# Attiny13.net
KiCad netlist of a schematic drawn in EAGLE
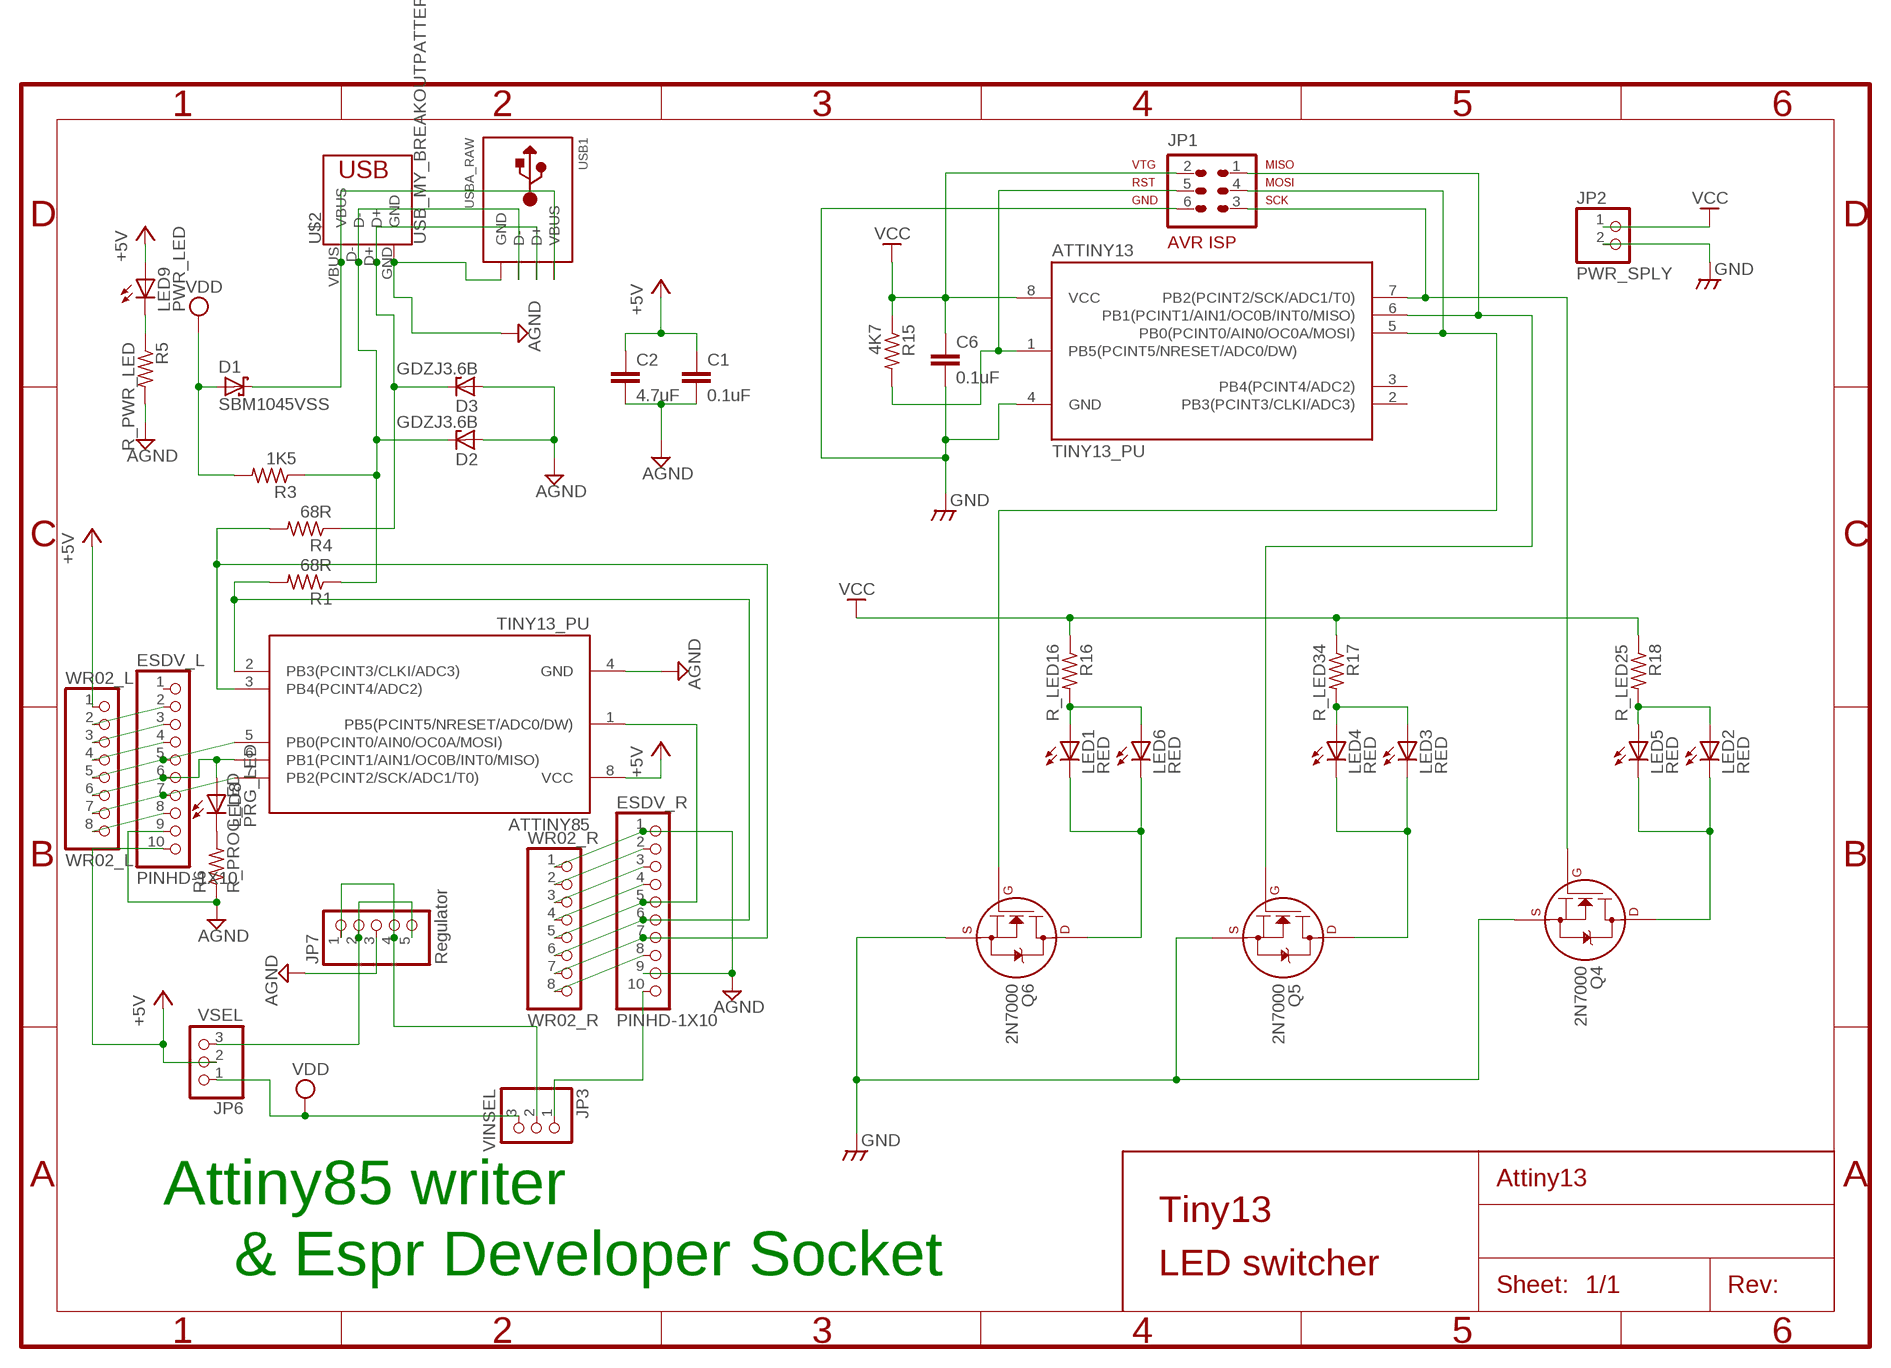
[diagram p0: schematic, sheet 1]

(export (version "E")
  (design (tool "Eeschema 10.0.6"))
  (components
    (comp (ref "ATTINY13")
      (value "TINY13_PU")
      (footprint "eagle-import:TINY_DIL08")
      (libsource (lib "eagle-import") (part "TINY13_PU"))
    )
    (comp (ref "ATTINY85")
      (value "TINY13_PU")
      (footprint "eagle-import:TINY_DIL08")
      (libsource (lib "eagle-import") (part "TINY13_PU"))
    )
    (comp (ref "C1")
      (value "0.1uF")
      (footprint "eagle-import:C050-025X075")
      (libsource (lib "eagle-import") (part "C-EU050-025X075"))
    )
    (comp (ref "C2")
      (value "4.7uF")
      (footprint "eagle-import:C050-025X075")
      (libsource (lib "eagle-import") (part "C-EU050-025X075"))
    )
    (comp (ref "C6")
      (value "0.1uF")
      (footprint "eagle-import:C050-025X075")
      (libsource (lib "eagle-import") (part "C-EU050-025X075"))
    )
    (comp (ref "D1")
      (value "SBM1045VSS")
      (footprint "eagle-import:DO41-10")
      (libsource (lib "eagle-import") (part "SCHOTTKY-DIODEDO41"))
    )
    (comp (ref "D2")
      (value "GDZJ3.6B")
      (footprint "eagle-import:DO34Z7")
      (libsource (lib "eagle-import") (part "ZENER-DIODEDO34-7"))
    )
    (comp (ref "D3")
      (value "GDZJ3.6B")
      (footprint "eagle-import:DO34Z7")
      (libsource (lib "eagle-import") (part "ZENER-DIODEDO34-7"))
    )
    (comp (ref "ESDV_L")
      (value "PINHD-1X10")
      (footprint "eagle-import:1X10-BIG")
      (libsource (lib "eagle-import") (part "PINHD-1X10"))
    )
    (comp (ref "ESDV_R")
      (value "PINHD-1X10")
      (footprint "eagle-import:1X10-BIG")
      (libsource (lib "eagle-import") (part "PINHD-1X10"))
    )
    (comp (ref "JP1")
      (value "AVR-ISP-6")
      (footprint "eagle-import:AVR-ISP-6")
      (libsource (lib "eagle-import") (part "AVR-ISP-6"))
    )
    (comp (ref "JP2")
      (value "PWR_SPLY")
      (footprint "eagle-import:1X02")
      (libsource (lib "eagle-import") (part "PINHD-1X2"))
    )
    (comp (ref "JP3")
      (value "VINSEL")
      (footprint "eagle-import:1X03")
      (libsource (lib "eagle-import") (part "PINHD-1X3"))
    )
    (comp (ref "JP6")
      (value "VSEL")
      (footprint "eagle-import:1X03")
      (libsource (lib "eagle-import") (part "PINHD-1X3"))
    )
    (comp (ref "JP7")
      (value "Regulator")
      (footprint "eagle-import:1X05")
      (libsource (lib "eagle-import") (part "PINHD-1X5"))
    )
    (comp (ref "LED1")
      (value "RED")
      (footprint "eagle-import:SFH480")
      (libsource (lib "eagle-import") (part "led_LEDSFH480"))
    )
    (comp (ref "LED2")
      (value "RED")
      (footprint "eagle-import:SFH480")
      (libsource (lib "eagle-import") (part "led_LEDSFH480"))
    )
    (comp (ref "LED3")
      (value "RED")
      (footprint "eagle-import:SFH480")
      (libsource (lib "eagle-import") (part "led_LEDSFH480"))
    )
    (comp (ref "LED4")
      (value "RED")
      (footprint "eagle-import:SFH480")
      (libsource (lib "eagle-import") (part "led_LEDSFH480"))
    )
    (comp (ref "LED5")
      (value "RED")
      (footprint "eagle-import:SFH480")
      (libsource (lib "eagle-import") (part "led_LEDSFH480"))
    )
    (comp (ref "LED6")
      (value "RED")
      (footprint "eagle-import:SFH480")
      (libsource (lib "eagle-import") (part "led_LEDSFH480"))
    )
    (comp (ref "LED8")
      (value "PRG_LED")
      (footprint "eagle-import:SFH480")
      (libsource (lib "eagle-import") (part "LEDSFH480"))
    )
    (comp (ref "LED9")
      (value "PWR_LED")
      (footprint "eagle-import:SFH480")
      (libsource (lib "eagle-import") (part "LEDSFH480"))
    )
    (comp (ref "Q4")
      (value "2N7000")
      (footprint "eagle-import:TO-92")
      (libsource (lib "eagle-import") (part "2N700_TO920"))
    )
    (comp (ref "Q5")
      (value "2N7000")
      (footprint "eagle-import:TO-92")
      (libsource (lib "eagle-import") (part "2N700_TO920"))
    )
    (comp (ref "Q6")
      (value "2N7000")
      (footprint "eagle-import:TO-92")
      (libsource (lib "eagle-import") (part "2N700_TO920"))
    )
    (comp (ref "R1")
      (value "68R")
      (footprint "eagle-import:0204_7")
      (libsource (lib "eagle-import") (part "R-US_0204/7"))
    )
    (comp (ref "R3")
      (value "1K5")
      (footprint "eagle-import:0204_7")
      (libsource (lib "eagle-import") (part "R-US_0204/7"))
    )
    (comp (ref "R4")
      (value "68R")
      (footprint "eagle-import:0204_7")
      (libsource (lib "eagle-import") (part "R-US_0204/7"))
    )
    (comp (ref "R5")
      (value "R_PWR_LED")
      (footprint "eagle-import:0204_7")
      (libsource (lib "eagle-import") (part "R-US_0204/7"))
    )
    (comp (ref "R6")
      (value "R_PROG_LED")
      (footprint "eagle-import:0204_7")
      (libsource (lib "eagle-import") (part "R-US_0204/7"))
    )
    (comp (ref "R15")
      (value "4K7")
      (footprint "eagle-import:0204_7")
      (libsource (lib "eagle-import") (part "R-US_0204/7"))
    )
    (comp (ref "R16")
      (value "R_LED16")
      (footprint "eagle-import:0204_7")
      (libsource (lib "eagle-import") (part "R-US_0204/7"))
    )
    (comp (ref "R17")
      (value "R_LED34")
      (footprint "eagle-import:0204_7")
      (libsource (lib "eagle-import") (part "R-US_0204/7"))
    )
    (comp (ref "R18")
      (value "R_LED25")
      (footprint "eagle-import:0204_7")
      (libsource (lib "eagle-import") (part "R-US_0204/7"))
    )
    (comp (ref "U$2")
      (value "USB_MY_BREAKOUTPATTERN2")
      (footprint "eagle-import:USB_MY_BREAKOUT2")
      (libsource (lib "eagle-import") (part "USB_MY_BREAKOUTPATTERN2"))
    )
    (comp (ref "USB1")
      (value "USBA_RAW")
      (footprint "eagle-import:USBA_RAW")
      (libsource (lib "eagle-import") (part "USBA_RAW"))
    )
    (comp (ref "WR02_L")
      (value "WR02_L")
      (footprint "eagle-import:1X08-BIG")
      (libsource (lib "eagle-import") (part "PINHD-1X8BIG"))
    )
    (comp (ref "WR02_R")
      (value "WR02_R")
      (footprint "eagle-import:1X08-BIG")
      (libsource (lib "eagle-import") (part "PINHD-1X8BIG"))
    )
  )
  (nets
    (net (code "1") (name "+5V") (class "Default")
      (node (ref "ATTINY85") (pin "8") (pinfunction "VCC_8") (pintype "power_in"))
      (node (ref "C1") (pin "1") (pinfunction "1_1") (pintype "passive"))
      (node (ref "C2") (pin "1") (pinfunction "1_1") (pintype "passive"))
      (node (ref "ESDV_L") (pin "10") (pinfunction "10_10") (pintype "passive"))
      (node (ref "JP6") (pin "2") (pinfunction "2_2") (pintype "passive"))
      (node (ref "LED9") (pin "A") (pinfunction "A_A") (pintype "passive"))
      (node (ref "WR02_L") (pin "1") (pinfunction "1_1") (pintype "passive"))
    )
    (net (code "2") (name "AGND") (class "Default")
      (node (ref "ATTINY85") (pin "4") (pinfunction "GND_4") (pintype "power_in"))
      (node (ref "C1") (pin "2") (pinfunction "2_2") (pintype "passive"))
      (node (ref "C2") (pin "2") (pinfunction "2_2") (pintype "passive"))
      (node (ref "D2") (pin "A") (pinfunction "A_A") (pintype "passive"))
      (node (ref "D3") (pin "A") (pinfunction "A_A") (pintype "passive"))
      (node (ref "ESDV_L") (pin "9") (pinfunction "9_9") (pintype "passive"))
      (node (ref "ESDV_R") (pin "1") (pinfunction "1_1") (pintype "passive"))
      (node (ref "ESDV_R") (pin "9") (pinfunction "9_9") (pintype "passive"))
      (node (ref "JP7") (pin "3") (pinfunction "3_3") (pintype "passive"))
      (node (ref "R5") (pin "2") (pinfunction "2_2") (pintype "passive"))
      (node (ref "R6") (pin "1") (pinfunction "1_1") (pintype "passive"))
      (node (ref "U$2") (pin "GND") (pinfunction "GND_GND") (pintype "power_in"))
      (node (ref "USB1") (pin "GND") (pinfunction "GND_GND") (pintype "power_in"))
      (node (ref "WR02_R") (pin "1") (pinfunction "1_1") (pintype "passive"))
    )
    (net (code "3") (name "GND") (class "Default")
      (node (ref "ATTINY13") (pin "4") (pinfunction "GND_4") (pintype "power_in"))
      (node (ref "C6") (pin "2") (pinfunction "2_2") (pintype "passive"))
      (node (ref "JP1") (pin "6") (pinfunction "6_6") (pintype "passive"))
      (node (ref "JP2") (pin "2") (pinfunction "2_2") (pintype "passive"))
      (node (ref "Q4") (pin "1") (pinfunction "S_1") (pintype "bidirectional"))
      (node (ref "Q5") (pin "1") (pinfunction "S_1") (pintype "bidirectional"))
      (node (ref "Q6") (pin "1") (pinfunction "S_1") (pintype "bidirectional"))
    )
    (net (code "4") (name "Net-(ATTINY13-PB0(PCINT0{slash}AIN0{slash}OC0A{slash}MOSI))") (class "Default")
      (node (ref "ATTINY13") (pin "5") (pinfunction "PB0(PCINT0/AIN0/OC0A/MOSI)_5") (pintype "bidirectional"))
      (node (ref "JP1") (pin "4") (pinfunction "4_4") (pintype "passive"))
      (node (ref "Q6") (pin "2") (pinfunction "G_2") (pintype "tri_state"))
    )
    (net (code "5") (name "Net-(ATTINY13-PB1(PCINT1{slash}AIN1{slash}OC0B{slash}INT0{slash}MISO))") (class "Default")
      (node (ref "ATTINY13") (pin "6") (pinfunction "PB1(PCINT1/AIN1/OC0B/INT0/MISO)_6") (pintype "bidirectional"))
      (node (ref "JP1") (pin "1") (pinfunction "1_1") (pintype "passive"))
      (node (ref "Q5") (pin "2") (pinfunction "G_2") (pintype "tri_state"))
    )
    (net (code "6") (name "Net-(ATTINY13-PB2(PCINT2{slash}SCK{slash}ADC1{slash}T0))") (class "Default")
      (node (ref "ATTINY13") (pin "7") (pinfunction "PB2(PCINT2/SCK/ADC1/T0)_7") (pintype "bidirectional"))
      (node (ref "JP1") (pin "3") (pinfunction "3_3") (pintype "passive"))
      (node (ref "Q4") (pin "2") (pinfunction "G_2") (pintype "tri_state"))
    )
    (net (code "7") (name "Net-(ATTINY13-PB5(PCINT5{slash}NRESET{slash}ADC0{slash}DW))") (class "Default")
      (node (ref "ATTINY13") (pin "1") (pinfunction "PB5(PCINT5/NRESET/ADC0/DW)_1") (pintype "bidirectional"))
      (node (ref "JP1") (pin "5") (pinfunction "5_5") (pintype "passive"))
      (node (ref "R15") (pin "2") (pinfunction "2_2") (pintype "passive"))
    )
    (net (code "8") (name "Net-(ATTINY85-PB0(PCINT0{slash}AIN0{slash}OC0A{slash}MOSI))") (class "Default")
      (node (ref "ATTINY85") (pin "5") (pinfunction "PB0(PCINT0/AIN0/OC0A/MOSI)_5") (pintype "bidirectional"))
      (node (ref "ESDV_L") (pin "5") (pinfunction "5_5") (pintype "passive"))
      (node (ref "WR02_L") (pin "5") (pinfunction "5_5") (pintype "passive"))
    )
    (net (code "9") (name "Net-(ATTINY85-PB1(PCINT1{slash}AIN1{slash}OC0B{slash}INT0{slash}MISO))") (class "Default")
      (node (ref "ATTINY85") (pin "6") (pinfunction "PB1(PCINT1/AIN1/OC0B/INT0/MISO)_6") (pintype "bidirectional"))
      (node (ref "ESDV_L") (pin "6") (pinfunction "6_6") (pintype "passive"))
      (node (ref "LED8") (pin "A") (pinfunction "A_A") (pintype "passive"))
      (node (ref "WR02_L") (pin "6") (pinfunction "6_6") (pintype "passive"))
    )
    (net (code "10") (name "Net-(ATTINY85-PB2(PCINT2{slash}SCK{slash}ADC1{slash}T0))") (class "Default")
      (node (ref "ATTINY85") (pin "7") (pinfunction "PB2(PCINT2/SCK/ADC1/T0)_7") (pintype "bidirectional"))
      (node (ref "ESDV_L") (pin "7") (pinfunction "7_7") (pintype "passive"))
      (node (ref "WR02_L") (pin "7") (pinfunction "7_7") (pintype "passive"))
    )
    (net (code "11") (name "Net-(ATTINY85-PB3(PCINT3{slash}CLKI{slash}ADC3))") (class "Default")
      (node (ref "ATTINY85") (pin "2") (pinfunction "PB3(PCINT3/CLKI/ADC3)_2") (pintype "bidirectional"))
      (node (ref "ESDV_R") (pin "6") (pinfunction "6_6") (pintype "passive"))
      (node (ref "R1") (pin "2") (pinfunction "2_2") (pintype "passive"))
      (node (ref "WR02_R") (pin "6") (pinfunction "6_6") (pintype "passive"))
    )
    (net (code "12") (name "Net-(ATTINY85-PB4(PCINT4{slash}ADC2))") (class "Default")
      (node (ref "ATTINY85") (pin "3") (pinfunction "PB4(PCINT4/ADC2)_3") (pintype "bidirectional"))
      (node (ref "ESDV_R") (pin "7") (pinfunction "7_7") (pintype "passive"))
      (node (ref "R4") (pin "2") (pinfunction "2_2") (pintype "passive"))
      (node (ref "WR02_R") (pin "7") (pinfunction "7_7") (pintype "passive"))
    )
    (net (code "13") (name "Net-(ATTINY85-PB5(PCINT5{slash}NRESET{slash}ADC0{slash}DW))") (class "Default")
      (node (ref "ATTINY85") (pin "1") (pinfunction "PB5(PCINT5/NRESET/ADC0/DW)_1") (pintype "bidirectional"))
      (node (ref "ESDV_R") (pin "5") (pinfunction "5_5") (pintype "passive"))
      (node (ref "WR02_R") (pin "5") (pinfunction "5_5") (pintype "passive"))
    )
    (net (code "14") (name "Net-(D1-PadC)") (class "Default")
      (node (ref "D1") (pin "C") (pinfunction "C_C") (pintype "passive"))
      (node (ref "U$2") (pin "VBUS") (pinfunction "VBUS_VBUS") (pintype "power_in"))
      (node (ref "USB1") (pin "VBUS") (pinfunction "VBUS_VBUS") (pintype "power_in"))
    )
    (net (code "15") (name "Net-(D2-PadC)") (class "Default")
      (node (ref "D2") (pin "C") (pinfunction "C_C") (pintype "passive"))
      (node (ref "R1") (pin "1") (pinfunction "1_1") (pintype "passive"))
      (node (ref "R3") (pin "1") (pinfunction "1_1") (pintype "passive"))
      (node (ref "U$2") (pin "D-") (pinfunction "D-_D-") (pintype "bidirectional"))
      (node (ref "USB1") (pin "D-") (pinfunction "D-_D-") (pintype "bidirectional"))
    )
    (net (code "16") (name "Net-(D3-PadC)") (class "Default")
      (node (ref "D3") (pin "C") (pinfunction "C_C") (pintype "passive"))
      (node (ref "R4") (pin "1") (pinfunction "1_1") (pintype "passive"))
      (node (ref "U$2") (pin "D+") (pinfunction "D+_D+") (pintype "bidirectional"))
      (node (ref "USB1") (pin "D+") (pinfunction "D+_D+") (pintype "bidirectional"))
    )
    (net (code "17") (name "Net-(ESDV_L-Pad2)") (class "Default")
      (node (ref "ESDV_L") (pin "2") (pinfunction "2_2") (pintype "passive"))
      (node (ref "WR02_L") (pin "2") (pinfunction "2_2") (pintype "passive"))
    )
    (net (code "18") (name "Net-(ESDV_L-Pad3)") (class "Default")
      (node (ref "ESDV_L") (pin "3") (pinfunction "3_3") (pintype "passive"))
      (node (ref "WR02_L") (pin "3") (pinfunction "3_3") (pintype "passive"))
    )
    (net (code "19") (name "Net-(ESDV_L-Pad4)") (class "Default")
      (node (ref "ESDV_L") (pin "4") (pinfunction "4_4") (pintype "passive"))
      (node (ref "WR02_L") (pin "4") (pinfunction "4_4") (pintype "passive"))
    )
    (net (code "20") (name "Net-(ESDV_L-Pad8)") (class "Default")
      (node (ref "ESDV_L") (pin "8") (pinfunction "8_8") (pintype "passive"))
      (node (ref "WR02_L") (pin "8") (pinfunction "8_8") (pintype "passive"))
    )
    (net (code "21") (name "Net-(ESDV_R-Pad2)") (class "Default")
      (node (ref "ESDV_R") (pin "2") (pinfunction "2_2") (pintype "passive"))
      (node (ref "WR02_R") (pin "2") (pinfunction "2_2") (pintype "passive"))
    )
    (net (code "22") (name "Net-(ESDV_R-Pad3)") (class "Default")
      (node (ref "ESDV_R") (pin "3") (pinfunction "3_3") (pintype "passive"))
      (node (ref "WR02_R") (pin "3") (pinfunction "3_3") (pintype "passive"))
    )
    (net (code "23") (name "Net-(ESDV_R-Pad4)") (class "Default")
      (node (ref "ESDV_R") (pin "4") (pinfunction "4_4") (pintype "passive"))
      (node (ref "WR02_R") (pin "4") (pinfunction "4_4") (pintype "passive"))
    )
    (net (code "24") (name "Net-(ESDV_R-Pad8)") (class "Default")
      (node (ref "ESDV_R") (pin "8") (pinfunction "8_8") (pintype "passive"))
      (node (ref "WR02_R") (pin "8") (pinfunction "8_8") (pintype "passive"))
    )
    (net (code "25") (name "Net-(ESDV_R-Pad10)") (class "Default")
      (node (ref "ESDV_R") (pin "10") (pinfunction "10_10") (pintype "passive"))
      (node (ref "JP3") (pin "1") (pinfunction "1_1") (pintype "passive"))
    )
    (net (code "26") (name "Net-(JP3-Pad2)") (class "Default")
      (node (ref "JP3") (pin "2") (pinfunction "2_2") (pintype "passive"))
      (node (ref "JP7") (pin "1") (pinfunction "1_1") (pintype "passive"))
      (node (ref "JP7") (pin "4") (pinfunction "4_4") (pintype "passive"))
    )
    (net (code "27") (name "Net-(JP6-Pad3)") (class "Default")
      (node (ref "JP6") (pin "3") (pinfunction "3_3") (pintype "passive"))
      (node (ref "JP7") (pin "2") (pinfunction "2_2") (pintype "passive"))
      (node (ref "JP7") (pin "5") (pinfunction "5_5") (pintype "passive"))
    )
    (net (code "28") (name "Net-(LED1-C)") (class "Default")
      (node (ref "LED1") (pin "K") (pinfunction "C_K") (pintype "passive"))
      (node (ref "LED6") (pin "K") (pinfunction "C_K") (pintype "passive"))
      (node (ref "Q6") (pin "3") (pinfunction "D_3") (pintype "bidirectional"))
    )
    (net (code "29") (name "Net-(LED1-PadA)") (class "Default")
      (node (ref "LED1") (pin "A") (pinfunction "A_A") (pintype "passive"))
      (node (ref "LED6") (pin "A") (pinfunction "A_A") (pintype "passive"))
      (node (ref "R16") (pin "2") (pinfunction "2_2") (pintype "passive"))
    )
    (net (code "30") (name "Net-(LED2-C)") (class "Default")
      (node (ref "LED2") (pin "K") (pinfunction "C_K") (pintype "passive"))
      (node (ref "LED5") (pin "K") (pinfunction "C_K") (pintype "passive"))
      (node (ref "Q4") (pin "3") (pinfunction "D_3") (pintype "bidirectional"))
    )
    (net (code "31") (name "Net-(LED2-PadA)") (class "Default")
      (node (ref "LED2") (pin "A") (pinfunction "A_A") (pintype "passive"))
      (node (ref "LED5") (pin "A") (pinfunction "A_A") (pintype "passive"))
      (node (ref "R18") (pin "2") (pinfunction "2_2") (pintype "passive"))
    )
    (net (code "32") (name "Net-(LED3-C)") (class "Default")
      (node (ref "LED3") (pin "K") (pinfunction "C_K") (pintype "passive"))
      (node (ref "LED4") (pin "K") (pinfunction "C_K") (pintype "passive"))
      (node (ref "Q5") (pin "3") (pinfunction "D_3") (pintype "bidirectional"))
    )
    (net (code "33") (name "Net-(LED3-PadA)") (class "Default")
      (node (ref "LED3") (pin "A") (pinfunction "A_A") (pintype "passive"))
      (node (ref "LED4") (pin "A") (pinfunction "A_A") (pintype "passive"))
      (node (ref "R17") (pin "2") (pinfunction "2_2") (pintype "passive"))
    )
    (net (code "34") (name "Net-(LED8-C)") (class "Default")
      (node (ref "LED8") (pin "K") (pinfunction "C_K") (pintype "passive"))
      (node (ref "R6") (pin "2") (pinfunction "2_2") (pintype "passive"))
    )
    (net (code "35") (name "Net-(LED9-C)") (class "Default")
      (node (ref "LED9") (pin "K") (pinfunction "C_K") (pintype "passive"))
      (node (ref "R5") (pin "1") (pinfunction "1_1") (pintype "passive"))
    )
    (net (code "36") (name "VCC") (class "Default")
      (node (ref "ATTINY13") (pin "8") (pinfunction "VCC_8") (pintype "power_in"))
      (node (ref "C6") (pin "1") (pinfunction "1_1") (pintype "passive"))
      (node (ref "JP1") (pin "2") (pinfunction "2_2") (pintype "passive"))
      (node (ref "JP2") (pin "1") (pinfunction "1_1") (pintype "passive"))
      (node (ref "R15") (pin "1") (pinfunction "1_1") (pintype "passive"))
      (node (ref "R16") (pin "1") (pinfunction "1_1") (pintype "passive"))
      (node (ref "R17") (pin "1") (pinfunction "1_1") (pintype "passive"))
      (node (ref "R18") (pin "1") (pinfunction "1_1") (pintype "passive"))
    )
    (net (code "37") (name "VDD") (class "Default")
      (node (ref "D1") (pin "A") (pinfunction "A_A") (pintype "passive"))
      (node (ref "JP3") (pin "3") (pinfunction "3_3") (pintype "passive"))
      (node (ref "JP6") (pin "1") (pinfunction "1_1") (pintype "passive"))
      (node (ref "R3") (pin "2") (pinfunction "2_2") (pintype "passive"))
    )
    (net (code "38") (name "unconnected-(ATTINY13-PB3(PCINT3{slash}CLKI{slash}ADC3)-Pad2)") (class "Default")
      (node (ref "ATTINY13") (pin "2") (pinfunction "PB3(PCINT3/CLKI/ADC3)_2") (pintype "bidirectional"))
    )
    (net (code "39") (name "unconnected-(ATTINY13-PB4(PCINT4{slash}ADC2)-Pad3)") (class "Default")
      (node (ref "ATTINY13") (pin "3") (pinfunction "PB4(PCINT4/ADC2)_3") (pintype "bidirectional"))
    )
    (net (code "40") (name "unconnected-(ESDV_L-Pad1)") (class "Default")
      (node (ref "ESDV_L") (pin "1") (pinfunction "1_1") (pintype "passive"))
    )
  )
)
